# six2two-switch3.net
KiCad netlist of a schematic drawn in EAGLE
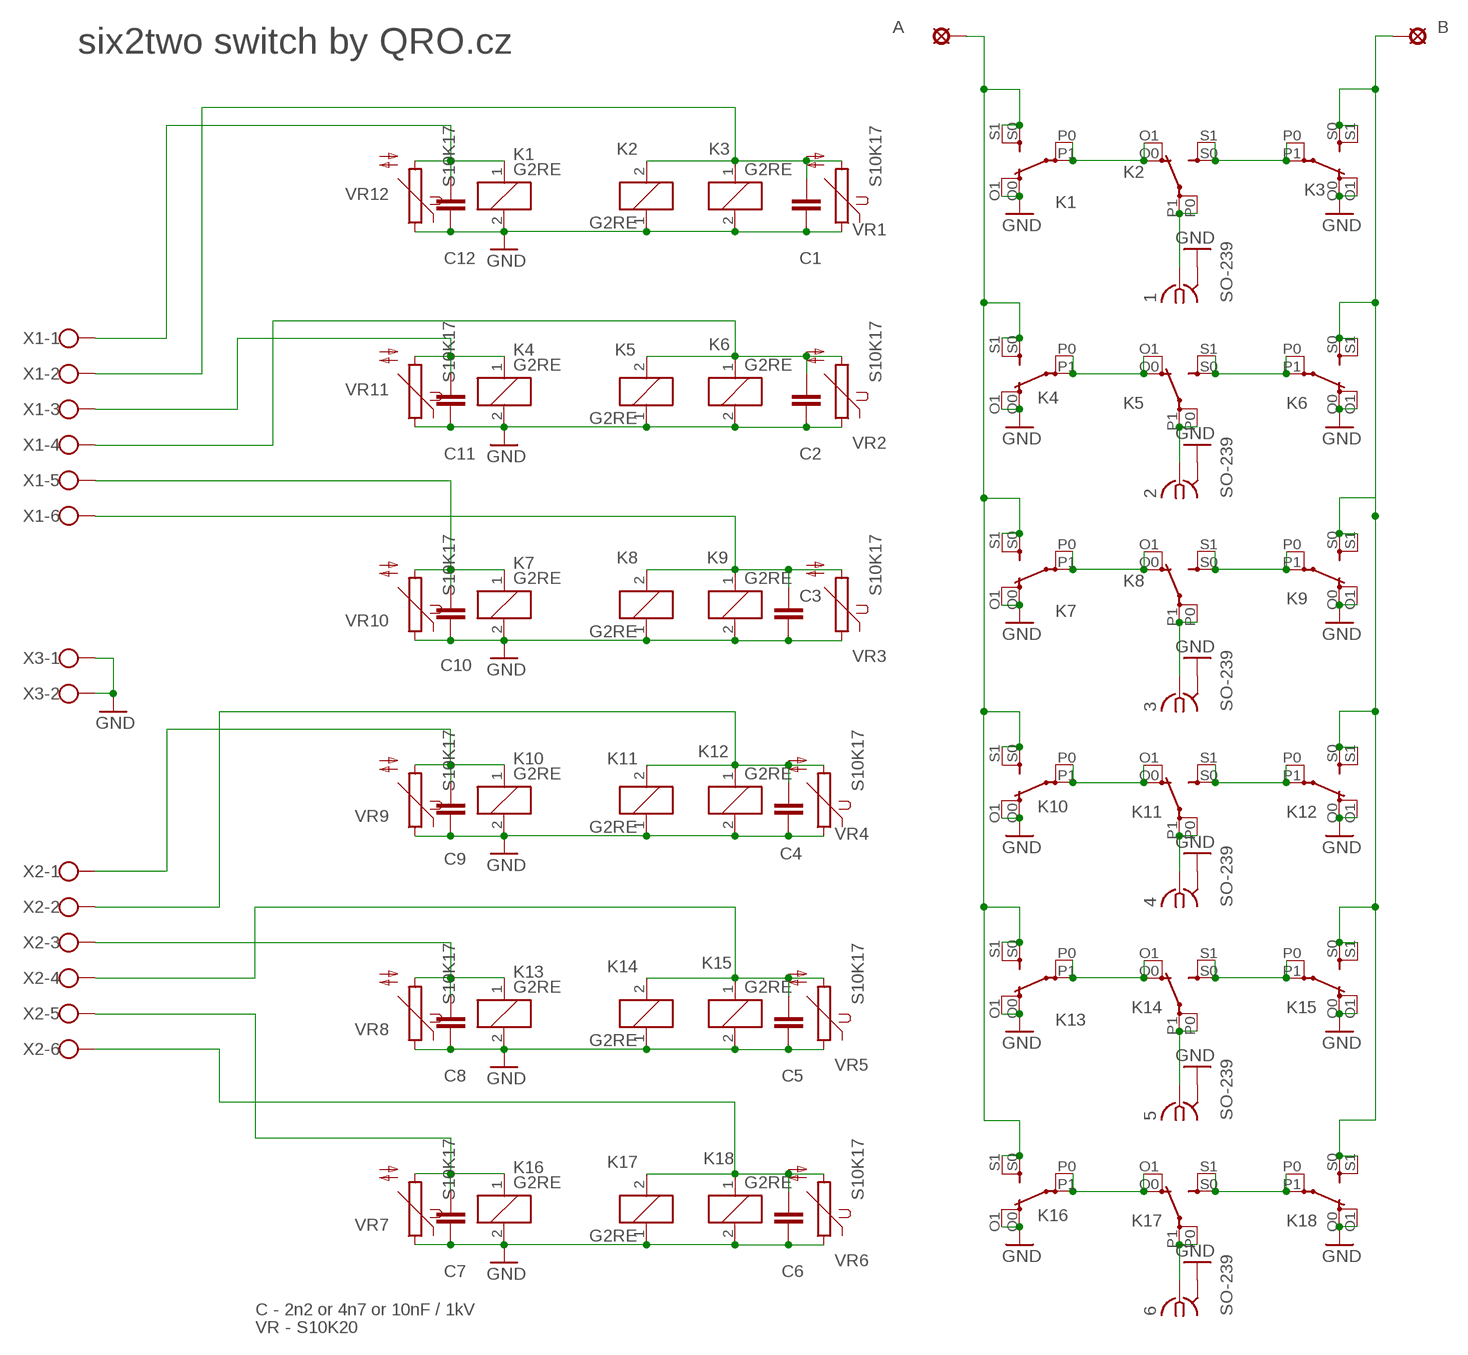
[diagram p0: schematic, sheet 1]

(export (version "E")
  (design (tool "Eeschema 10.0.6"))
  (components
    (comp (ref "1")
      (value "SO-239")
      (footprint "eagle-import:SO-239")
      (libsource (lib "eagle-import") (part "SO-239"))
    )
    (comp (ref "2")
      (value "SO-239")
      (footprint "eagle-import:SO-239")
      (libsource (lib "eagle-import") (part "SO-239"))
    )
    (comp (ref "3")
      (value "SO-239")
      (footprint "eagle-import:SO-239")
      (libsource (lib "eagle-import") (part "SO-239"))
    )
    (comp (ref "4")
      (value "SO-239")
      (footprint "eagle-import:SO-239")
      (libsource (lib "eagle-import") (part "SO-239"))
    )
    (comp (ref "5")
      (value "SO-239")
      (footprint "eagle-import:SO-239")
      (libsource (lib "eagle-import") (part "SO-239"))
    )
    (comp (ref "6")
      (value "SO-239")
      (footprint "eagle-import:SO-239")
      (libsource (lib "eagle-import") (part "SO-239"))
    )
    (comp (ref "A")
      (value "LSP13")
      (footprint "eagle-import:LSP13")
      (libsource (lib "eagle-import") (part "LSP13"))
    )
    (comp (ref "B")
      (value "LSP13")
      (footprint "eagle-import:LSP13")
      (libsource (lib "eagle-import") (part "LSP13"))
    )
    (comp (ref "C1")
      (value "C-EU075-032X103")
      (footprint "eagle-import:C075-032X103")
      (libsource (lib "eagle-import") (part "C-EU075-032X103"))
    )
    (comp (ref "C2")
      (value "C-EU075-032X103")
      (footprint "eagle-import:C075-032X103")
      (libsource (lib "eagle-import") (part "C-EU075-032X103"))
    )
    (comp (ref "C3")
      (value "C-EU075-032X103")
      (footprint "eagle-import:C075-032X103")
      (libsource (lib "eagle-import") (part "C-EU075-032X103"))
    )
    (comp (ref "C4")
      (value "C-EU075-032X103")
      (footprint "eagle-import:C075-032X103")
      (libsource (lib "eagle-import") (part "C-EU075-032X103"))
    )
    (comp (ref "C5")
      (value "C-EU075-032X103")
      (footprint "eagle-import:C075-032X103")
      (libsource (lib "eagle-import") (part "C-EU075-032X103"))
    )
    (comp (ref "C6")
      (value "C-EU075-032X103")
      (footprint "eagle-import:C075-032X103")
      (libsource (lib "eagle-import") (part "C-EU075-032X103"))
    )
    (comp (ref "C7")
      (value "C-EU075-032X103")
      (footprint "eagle-import:C075-032X103")
      (libsource (lib "eagle-import") (part "C-EU075-032X103"))
    )
    (comp (ref "C8")
      (value "C-EU075-032X103")
      (footprint "eagle-import:C075-032X103")
      (libsource (lib "eagle-import") (part "C-EU075-032X103"))
    )
    (comp (ref "C9")
      (value "C-EU075-032X103")
      (footprint "eagle-import:C075-032X103")
      (libsource (lib "eagle-import") (part "C-EU075-032X103"))
    )
    (comp (ref "C10")
      (value "C-EU075-032X103")
      (footprint "eagle-import:C075-032X103")
      (libsource (lib "eagle-import") (part "C-EU075-032X103"))
    )
    (comp (ref "C11")
      (value "C-EU075-032X103")
      (footprint "eagle-import:C075-032X103")
      (libsource (lib "eagle-import") (part "C-EU075-032X103"))
    )
    (comp (ref "C12")
      (value "C-EU075-032X103")
      (footprint "eagle-import:C075-032X103")
      (libsource (lib "eagle-import") (part "C-EU075-032X103"))
    )
    (comp (ref "K1")
      (value "G2RE")
      (footprint "eagle-import:G2RE")
      (libsource (lib "eagle-import") (part "G2RE"))
    )
    (comp (ref "K2")
      (value "G2RE")
      (footprint "eagle-import:G2RE")
      (libsource (lib "eagle-import") (part "G2RE"))
    )
    (comp (ref "K3")
      (value "G2RE")
      (footprint "eagle-import:G2RE")
      (libsource (lib "eagle-import") (part "G2RE"))
    )
    (comp (ref "K4")
      (value "G2RE")
      (footprint "eagle-import:G2RE")
      (libsource (lib "eagle-import") (part "G2RE"))
    )
    (comp (ref "K5")
      (value "G2RE")
      (footprint "eagle-import:G2RE")
      (libsource (lib "eagle-import") (part "G2RE"))
    )
    (comp (ref "K6")
      (value "G2RE")
      (footprint "eagle-import:G2RE")
      (libsource (lib "eagle-import") (part "G2RE"))
    )
    (comp (ref "K7")
      (value "G2RE")
      (footprint "eagle-import:G2RE")
      (libsource (lib "eagle-import") (part "G2RE"))
    )
    (comp (ref "K8")
      (value "G2RE")
      (footprint "eagle-import:G2RE")
      (libsource (lib "eagle-import") (part "G2RE"))
    )
    (comp (ref "K9")
      (value "G2RE")
      (footprint "eagle-import:G2RE")
      (libsource (lib "eagle-import") (part "G2RE"))
    )
    (comp (ref "K10")
      (value "G2RE")
      (footprint "eagle-import:G2RE")
      (libsource (lib "eagle-import") (part "G2RE"))
    )
    (comp (ref "K11")
      (value "G2RE")
      (footprint "eagle-import:G2RE")
      (libsource (lib "eagle-import") (part "G2RE"))
    )
    (comp (ref "K12")
      (value "G2RE")
      (footprint "eagle-import:G2RE")
      (libsource (lib "eagle-import") (part "G2RE"))
    )
    (comp (ref "K13")
      (value "G2RE")
      (footprint "eagle-import:G2RE")
      (libsource (lib "eagle-import") (part "G2RE"))
    )
    (comp (ref "K14")
      (value "G2RE")
      (footprint "eagle-import:G2RE")
      (libsource (lib "eagle-import") (part "G2RE"))
    )
    (comp (ref "K15")
      (value "G2RE")
      (footprint "eagle-import:G2RE")
      (libsource (lib "eagle-import") (part "G2RE"))
    )
    (comp (ref "K16")
      (value "G2RE")
      (footprint "eagle-import:G2RE")
      (libsource (lib "eagle-import") (part "G2RE"))
    )
    (comp (ref "K17")
      (value "G2RE")
      (footprint "eagle-import:G2RE")
      (libsource (lib "eagle-import") (part "G2RE"))
    )
    (comp (ref "K18")
      (value "G2RE")
      (footprint "eagle-import:G2RE")
      (libsource (lib "eagle-import") (part "G2RE"))
    )
    (comp (ref "VR1")
      (value "S10K17")
      (footprint "eagle-import:S10K17")
      (libsource (lib "eagle-import") (part "S10K17"))
    )
    (comp (ref "VR2")
      (value "S10K17")
      (footprint "eagle-import:S10K17")
      (libsource (lib "eagle-import") (part "S10K17"))
    )
    (comp (ref "VR3")
      (value "S10K17")
      (footprint "eagle-import:S10K17")
      (libsource (lib "eagle-import") (part "S10K17"))
    )
    (comp (ref "VR4")
      (value "S10K17")
      (footprint "eagle-import:S10K17")
      (libsource (lib "eagle-import") (part "S10K17"))
    )
    (comp (ref "VR5")
      (value "S10K17")
      (footprint "eagle-import:S10K17")
      (libsource (lib "eagle-import") (part "S10K17"))
    )
    (comp (ref "VR6")
      (value "S10K17")
      (footprint "eagle-import:S10K17")
      (libsource (lib "eagle-import") (part "S10K17"))
    )
    (comp (ref "VR7")
      (value "S10K17")
      (footprint "eagle-import:S10K17")
      (libsource (lib "eagle-import") (part "S10K17"))
    )
    (comp (ref "VR8")
      (value "S10K17")
      (footprint "eagle-import:S10K17")
      (libsource (lib "eagle-import") (part "S10K17"))
    )
    (comp (ref "VR9")
      (value "S10K17")
      (footprint "eagle-import:S10K17")
      (libsource (lib "eagle-import") (part "S10K17"))
    )
    (comp (ref "VR10")
      (value "S10K17")
      (footprint "eagle-import:S10K17")
      (libsource (lib "eagle-import") (part "S10K17"))
    )
    (comp (ref "VR11")
      (value "S10K17")
      (footprint "eagle-import:S10K17")
      (libsource (lib "eagle-import") (part "S10K17"))
    )
    (comp (ref "VR12")
      (value "S10K17")
      (footprint "eagle-import:S10K17")
      (libsource (lib "eagle-import") (part "S10K17"))
    )
    (comp (ref "X1")
      (value "W237-6")
      (footprint "eagle-import:W237-6")
      (libsource (lib "eagle-import") (part "W237-6"))
    )
    (comp (ref "X2")
      (value "W237-6")
      (footprint "eagle-import:W237-6")
      (libsource (lib "eagle-import") (part "W237-6"))
    )
    (comp (ref "X3")
      (value "W237-102")
      (footprint "eagle-import:W237-102")
      (fields (field (name "MPN") "237-102"))
      (libsource (lib "eagle-import") (part "W237-102"))
    )
  )
  (nets
    (net (code "1") (name "GND") (class "Default")
      (node (ref "1") (pin "P$2") (pinfunction "GND_P$2") (pintype "passive"))
      (node (ref "2") (pin "P$2") (pinfunction "GND_P$2") (pintype "passive"))
      (node (ref "3") (pin "P$2") (pinfunction "GND_P$2") (pintype "passive"))
      (node (ref "4") (pin "P$2") (pinfunction "GND_P$2") (pintype "passive"))
      (node (ref "5") (pin "P$2") (pinfunction "GND_P$2") (pintype "passive"))
      (node (ref "6") (pin "P$2") (pinfunction "GND_P$2") (pintype "passive"))
      (node (ref "C1") (pin "2") (pinfunction "2_2") (pintype "passive"))
      (node (ref "C10") (pin "2") (pinfunction "2_2") (pintype "passive"))
      (node (ref "C11") (pin "2") (pinfunction "2_2") (pintype "passive"))
      (node (ref "C12") (pin "2") (pinfunction "2_2") (pintype "passive"))
      (node (ref "C2") (pin "2") (pinfunction "2_2") (pintype "passive"))
      (node (ref "C3") (pin "2") (pinfunction "2_2") (pintype "passive"))
      (node (ref "C4") (pin "2") (pinfunction "2_2") (pintype "passive"))
      (node (ref "C5") (pin "2") (pinfunction "2_2") (pintype "passive"))
      (node (ref "C6") (pin "2") (pinfunction "2_2") (pintype "passive"))
      (node (ref "C7") (pin "2") (pinfunction "2_2") (pintype "passive"))
      (node (ref "C8") (pin "2") (pinfunction "2_2") (pintype "passive"))
      (node (ref "C9") (pin "2") (pinfunction "2_2") (pintype "passive"))
      (node (ref "K1") (pin "2") (pinfunction "2_2") (pintype "passive"))
      (node (ref "K1") (pin "O0") (pinfunction "O_O0") (pintype "passive"))
      (node (ref "K1") (pin "O1") (pinfunction "O_O1") (pintype "passive"))
      (node (ref "K10") (pin "2") (pinfunction "2_2") (pintype "passive"))
      (node (ref "K10") (pin "O0") (pinfunction "O_O0") (pintype "passive"))
      (node (ref "K10") (pin "O1") (pinfunction "O_O1") (pintype "passive"))
      (node (ref "K11") (pin "1") (pinfunction "1_1") (pintype "passive"))
      (node (ref "K12") (pin "2") (pinfunction "2_2") (pintype "passive"))
      (node (ref "K12") (pin "O0") (pinfunction "O_O0") (pintype "passive"))
      (node (ref "K12") (pin "O1") (pinfunction "O_O1") (pintype "passive"))
      (node (ref "K13") (pin "2") (pinfunction "2_2") (pintype "passive"))
      (node (ref "K13") (pin "O0") (pinfunction "O_O0") (pintype "passive"))
      (node (ref "K13") (pin "O1") (pinfunction "O_O1") (pintype "passive"))
      (node (ref "K14") (pin "1") (pinfunction "1_1") (pintype "passive"))
      (node (ref "K15") (pin "2") (pinfunction "2_2") (pintype "passive"))
      (node (ref "K15") (pin "O0") (pinfunction "O_O0") (pintype "passive"))
      (node (ref "K15") (pin "O1") (pinfunction "O_O1") (pintype "passive"))
      (node (ref "K16") (pin "2") (pinfunction "2_2") (pintype "passive"))
      (node (ref "K16") (pin "O0") (pinfunction "O_O0") (pintype "passive"))
      (node (ref "K16") (pin "O1") (pinfunction "O_O1") (pintype "passive"))
      (node (ref "K17") (pin "1") (pinfunction "1_1") (pintype "passive"))
      (node (ref "K18") (pin "2") (pinfunction "2_2") (pintype "passive"))
      (node (ref "K18") (pin "O0") (pinfunction "O_O0") (pintype "passive"))
      (node (ref "K18") (pin "O1") (pinfunction "O_O1") (pintype "passive"))
      (node (ref "K2") (pin "1") (pinfunction "1_1") (pintype "passive"))
      (node (ref "K3") (pin "2") (pinfunction "2_2") (pintype "passive"))
      (node (ref "K3") (pin "O0") (pinfunction "O_O0") (pintype "passive"))
      (node (ref "K3") (pin "O1") (pinfunction "O_O1") (pintype "passive"))
      (node (ref "K4") (pin "2") (pinfunction "2_2") (pintype "passive"))
      (node (ref "K4") (pin "O0") (pinfunction "O_O0") (pintype "passive"))
      (node (ref "K4") (pin "O1") (pinfunction "O_O1") (pintype "passive"))
      (node (ref "K5") (pin "1") (pinfunction "1_1") (pintype "passive"))
      (node (ref "K6") (pin "2") (pinfunction "2_2") (pintype "passive"))
      (node (ref "K6") (pin "O0") (pinfunction "O_O0") (pintype "passive"))
      (node (ref "K6") (pin "O1") (pinfunction "O_O1") (pintype "passive"))
      (node (ref "K7") (pin "2") (pinfunction "2_2") (pintype "passive"))
      (node (ref "K7") (pin "O0") (pinfunction "O_O0") (pintype "passive"))
      (node (ref "K7") (pin "O1") (pinfunction "O_O1") (pintype "passive"))
      (node (ref "K8") (pin "1") (pinfunction "1_1") (pintype "passive"))
      (node (ref "K9") (pin "2") (pinfunction "2_2") (pintype "passive"))
      (node (ref "K9") (pin "O0") (pinfunction "O_O0") (pintype "passive"))
      (node (ref "K9") (pin "O1") (pinfunction "O_O1") (pintype "passive"))
      (node (ref "VR1") (pin "1") (pinfunction "1_1") (pintype "passive"))
      (node (ref "VR10") (pin "1") (pinfunction "1_1") (pintype "passive"))
      (node (ref "VR11") (pin "1") (pinfunction "1_1") (pintype "passive"))
      (node (ref "VR12") (pin "1") (pinfunction "1_1") (pintype "passive"))
      (node (ref "VR2") (pin "1") (pinfunction "1_1") (pintype "passive"))
      (node (ref "VR3") (pin "1") (pinfunction "1_1") (pintype "passive"))
      (node (ref "VR4") (pin "1") (pinfunction "1_1") (pintype "passive"))
      (node (ref "VR5") (pin "1") (pinfunction "1_1") (pintype "passive"))
      (node (ref "VR6") (pin "1") (pinfunction "1_1") (pintype "passive"))
      (node (ref "VR7") (pin "1") (pinfunction "1_1") (pintype "passive"))
      (node (ref "VR8") (pin "1") (pinfunction "1_1") (pintype "passive"))
      (node (ref "VR9") (pin "1") (pinfunction "1_1") (pintype "passive"))
      (node (ref "X3") (pin "1") (pinfunction "KL_1") (pintype "passive"))
      (node (ref "X3") (pin "2") (pinfunction "KL_2") (pintype "passive"))
    )
    (net (code "2") (name "Net-(1-1)") (class "Default")
      (node (ref "1") (pin "P$1") (pinfunction "1_P$1") (pintype "passive"))
      (node (ref "K2") (pin "P0") (pinfunction "P_P0") (pintype "passive"))
      (node (ref "K2") (pin "P1") (pinfunction "P_P1") (pintype "passive"))
    )
    (net (code "3") (name "Net-(2-1)") (class "Default")
      (node (ref "2") (pin "P$1") (pinfunction "1_P$1") (pintype "passive"))
      (node (ref "K5") (pin "P0") (pinfunction "P_P0") (pintype "passive"))
      (node (ref "K5") (pin "P1") (pinfunction "P_P1") (pintype "passive"))
    )
    (net (code "4") (name "Net-(3-1)") (class "Default")
      (node (ref "3") (pin "P$1") (pinfunction "1_P$1") (pintype "passive"))
      (node (ref "K8") (pin "P0") (pinfunction "P_P0") (pintype "passive"))
      (node (ref "K8") (pin "P1") (pinfunction "P_P1") (pintype "passive"))
    )
    (net (code "5") (name "Net-(4-1)") (class "Default")
      (node (ref "4") (pin "P$1") (pinfunction "1_P$1") (pintype "passive"))
      (node (ref "K11") (pin "P0") (pinfunction "P_P0") (pintype "passive"))
      (node (ref "K11") (pin "P1") (pinfunction "P_P1") (pintype "passive"))
    )
    (net (code "6") (name "Net-(5-1)") (class "Default")
      (node (ref "5") (pin "P$1") (pinfunction "1_P$1") (pintype "passive"))
      (node (ref "K14") (pin "P0") (pinfunction "P_P0") (pintype "passive"))
      (node (ref "K14") (pin "P1") (pinfunction "P_P1") (pintype "passive"))
    )
    (net (code "7") (name "Net-(6-1)") (class "Default")
      (node (ref "6") (pin "P$1") (pinfunction "1_P$1") (pintype "passive"))
      (node (ref "K17") (pin "P0") (pinfunction "P_P0") (pintype "passive"))
      (node (ref "K17") (pin "P1") (pinfunction "P_P1") (pintype "passive"))
    )
    (net (code "8") (name "Net-(A-PadMP)") (class "Default")
      (node (ref "A") (pin "MP") (pinfunction "MP_MP") (pintype "passive"))
      (node (ref "K1") (pin "S0") (pinfunction "S_S0") (pintype "passive"))
      (node (ref "K1") (pin "S1") (pinfunction "S_S1") (pintype "passive"))
      (node (ref "K10") (pin "S0") (pinfunction "S_S0") (pintype "passive"))
      (node (ref "K10") (pin "S1") (pinfunction "S_S1") (pintype "passive"))
      (node (ref "K13") (pin "S0") (pinfunction "S_S0") (pintype "passive"))
      (node (ref "K13") (pin "S1") (pinfunction "S_S1") (pintype "passive"))
      (node (ref "K16") (pin "S0") (pinfunction "S_S0") (pintype "passive"))
      (node (ref "K16") (pin "S1") (pinfunction "S_S1") (pintype "passive"))
      (node (ref "K4") (pin "S0") (pinfunction "S_S0") (pintype "passive"))
      (node (ref "K4") (pin "S1") (pinfunction "S_S1") (pintype "passive"))
      (node (ref "K7") (pin "S0") (pinfunction "S_S0") (pintype "passive"))
      (node (ref "K7") (pin "S1") (pinfunction "S_S1") (pintype "passive"))
    )
    (net (code "9") (name "Net-(B-PadMP)") (class "Default")
      (node (ref "B") (pin "MP") (pinfunction "MP_MP") (pintype "passive"))
      (node (ref "K12") (pin "S0") (pinfunction "S_S0") (pintype "passive"))
      (node (ref "K12") (pin "S1") (pinfunction "S_S1") (pintype "passive"))
      (node (ref "K15") (pin "S0") (pinfunction "S_S0") (pintype "passive"))
      (node (ref "K15") (pin "S1") (pinfunction "S_S1") (pintype "passive"))
      (node (ref "K18") (pin "S0") (pinfunction "S_S0") (pintype "passive"))
      (node (ref "K18") (pin "S1") (pinfunction "S_S1") (pintype "passive"))
      (node (ref "K3") (pin "S0") (pinfunction "S_S0") (pintype "passive"))
      (node (ref "K3") (pin "S1") (pinfunction "S_S1") (pintype "passive"))
      (node (ref "K6") (pin "S0") (pinfunction "S_S0") (pintype "passive"))
      (node (ref "K6") (pin "S1") (pinfunction "S_S1") (pintype "passive"))
      (node (ref "K9") (pin "S0") (pinfunction "S_S0") (pintype "passive"))
      (node (ref "K9") (pin "S1") (pinfunction "S_S1") (pintype "passive"))
    )
    (net (code "10") (name "Net-(K1B-P-PadP0)") (class "Default")
      (node (ref "K1") (pin "P0") (pinfunction "P_P0") (pintype "passive"))
      (node (ref "K1") (pin "P1") (pinfunction "P_P1") (pintype "passive"))
      (node (ref "K2") (pin "O0") (pinfunction "O_O0") (pintype "passive"))
      (node (ref "K2") (pin "O1") (pinfunction "O_O1") (pintype "passive"))
    )
    (net (code "11") (name "Net-(K2B-S-PadS0)") (class "Default")
      (node (ref "K2") (pin "S0") (pinfunction "S_S0") (pintype "passive"))
      (node (ref "K2") (pin "S1") (pinfunction "S_S1") (pintype "passive"))
      (node (ref "K3") (pin "P0") (pinfunction "P_P0") (pintype "passive"))
      (node (ref "K3") (pin "P1") (pinfunction "P_P1") (pintype "passive"))
    )
    (net (code "12") (name "Net-(K4B-P-PadP0)") (class "Default")
      (node (ref "K4") (pin "P0") (pinfunction "P_P0") (pintype "passive"))
      (node (ref "K4") (pin "P1") (pinfunction "P_P1") (pintype "passive"))
      (node (ref "K5") (pin "O0") (pinfunction "O_O0") (pintype "passive"))
      (node (ref "K5") (pin "O1") (pinfunction "O_O1") (pintype "passive"))
    )
    (net (code "13") (name "Net-(K5B-S-PadS0)") (class "Default")
      (node (ref "K5") (pin "S0") (pinfunction "S_S0") (pintype "passive"))
      (node (ref "K5") (pin "S1") (pinfunction "S_S1") (pintype "passive"))
      (node (ref "K6") (pin "P0") (pinfunction "P_P0") (pintype "passive"))
      (node (ref "K6") (pin "P1") (pinfunction "P_P1") (pintype "passive"))
    )
    (net (code "14") (name "Net-(K7B-P-PadP0)") (class "Default")
      (node (ref "K7") (pin "P0") (pinfunction "P_P0") (pintype "passive"))
      (node (ref "K7") (pin "P1") (pinfunction "P_P1") (pintype "passive"))
      (node (ref "K8") (pin "O0") (pinfunction "O_O0") (pintype "passive"))
      (node (ref "K8") (pin "O1") (pinfunction "O_O1") (pintype "passive"))
    )
    (net (code "15") (name "Net-(K8B-S-PadS0)") (class "Default")
      (node (ref "K8") (pin "S0") (pinfunction "S_S0") (pintype "passive"))
      (node (ref "K8") (pin "S1") (pinfunction "S_S1") (pintype "passive"))
      (node (ref "K9") (pin "P0") (pinfunction "P_P0") (pintype "passive"))
      (node (ref "K9") (pin "P1") (pinfunction "P_P1") (pintype "passive"))
    )
    (net (code "16") (name "Net-(K10B-P-PadP0)") (class "Default")
      (node (ref "K10") (pin "P0") (pinfunction "P_P0") (pintype "passive"))
      (node (ref "K10") (pin "P1") (pinfunction "P_P1") (pintype "passive"))
      (node (ref "K11") (pin "O0") (pinfunction "O_O0") (pintype "passive"))
      (node (ref "K11") (pin "O1") (pinfunction "O_O1") (pintype "passive"))
    )
    (net (code "17") (name "Net-(K11B-S-PadS0)") (class "Default")
      (node (ref "K11") (pin "S0") (pinfunction "S_S0") (pintype "passive"))
      (node (ref "K11") (pin "S1") (pinfunction "S_S1") (pintype "passive"))
      (node (ref "K12") (pin "P0") (pinfunction "P_P0") (pintype "passive"))
      (node (ref "K12") (pin "P1") (pinfunction "P_P1") (pintype "passive"))
    )
    (net (code "18") (name "Net-(K13B-P-PadP0)") (class "Default")
      (node (ref "K13") (pin "P0") (pinfunction "P_P0") (pintype "passive"))
      (node (ref "K13") (pin "P1") (pinfunction "P_P1") (pintype "passive"))
      (node (ref "K14") (pin "O0") (pinfunction "O_O0") (pintype "passive"))
      (node (ref "K14") (pin "O1") (pinfunction "O_O1") (pintype "passive"))
    )
    (net (code "19") (name "Net-(K14B-S-PadS0)") (class "Default")
      (node (ref "K14") (pin "S0") (pinfunction "S_S0") (pintype "passive"))
      (node (ref "K14") (pin "S1") (pinfunction "S_S1") (pintype "passive"))
      (node (ref "K15") (pin "P0") (pinfunction "P_P0") (pintype "passive"))
      (node (ref "K15") (pin "P1") (pinfunction "P_P1") (pintype "passive"))
    )
    (net (code "20") (name "Net-(K16B-P-PadP0)") (class "Default")
      (node (ref "K16") (pin "P0") (pinfunction "P_P0") (pintype "passive"))
      (node (ref "K16") (pin "P1") (pinfunction "P_P1") (pintype "passive"))
      (node (ref "K17") (pin "O0") (pinfunction "O_O0") (pintype "passive"))
      (node (ref "K17") (pin "O1") (pinfunction "O_O1") (pintype "passive"))
    )
    (net (code "21") (name "Net-(K17B-S-PadS0)") (class "Default")
      (node (ref "K17") (pin "S0") (pinfunction "S_S0") (pintype "passive"))
      (node (ref "K17") (pin "S1") (pinfunction "S_S1") (pintype "passive"))
      (node (ref "K18") (pin "P0") (pinfunction "P_P0") (pintype "passive"))
      (node (ref "K18") (pin "P1") (pinfunction "P_P1") (pintype "passive"))
    )
    (net (code "22") (name "Net-(X1A-KL)") (class "Default")
      (node (ref "C12") (pin "1") (pinfunction "1_1") (pintype "passive"))
      (node (ref "K1") (pin "1") (pinfunction "1_1") (pintype "passive"))
      (node (ref "VR12") (pin "2") (pinfunction "2_2") (pintype "passive"))
      (node (ref "X1") (pin "1") (pinfunction "KL_1") (pintype "passive"))
    )
    (net (code "23") (name "Net-(X1B-KL)") (class "Default")
      (node (ref "C1") (pin "1") (pinfunction "1_1") (pintype "passive"))
      (node (ref "K2") (pin "2") (pinfunction "2_2") (pintype "passive"))
      (node (ref "K3") (pin "1") (pinfunction "1_1") (pintype "passive"))
      (node (ref "VR1") (pin "2") (pinfunction "2_2") (pintype "passive"))
      (node (ref "X1") (pin "2") (pinfunction "KL_2") (pintype "passive"))
    )
    (net (code "24") (name "Net-(X1C-KL)") (class "Default")
      (node (ref "C11") (pin "1") (pinfunction "1_1") (pintype "passive"))
      (node (ref "K4") (pin "1") (pinfunction "1_1") (pintype "passive"))
      (node (ref "VR11") (pin "2") (pinfunction "2_2") (pintype "passive"))
      (node (ref "X1") (pin "3") (pinfunction "KL_3") (pintype "passive"))
    )
    (net (code "25") (name "Net-(X1D-KL)") (class "Default")
      (node (ref "C2") (pin "1") (pinfunction "1_1") (pintype "passive"))
      (node (ref "K5") (pin "2") (pinfunction "2_2") (pintype "passive"))
      (node (ref "K6") (pin "1") (pinfunction "1_1") (pintype "passive"))
      (node (ref "VR2") (pin "2") (pinfunction "2_2") (pintype "passive"))
      (node (ref "X1") (pin "4") (pinfunction "KL_4") (pintype "passive"))
    )
    (net (code "26") (name "Net-(X1E-KL)") (class "Default")
      (node (ref "C10") (pin "1") (pinfunction "1_1") (pintype "passive"))
      (node (ref "K7") (pin "1") (pinfunction "1_1") (pintype "passive"))
      (node (ref "VR10") (pin "2") (pinfunction "2_2") (pintype "passive"))
      (node (ref "X1") (pin "5") (pinfunction "KL_5") (pintype "passive"))
    )
    (net (code "27") (name "Net-(X1F-KL)") (class "Default")
      (node (ref "C3") (pin "1") (pinfunction "1_1") (pintype "passive"))
      (node (ref "K8") (pin "2") (pinfunction "2_2") (pintype "passive"))
      (node (ref "K9") (pin "1") (pinfunction "1_1") (pintype "passive"))
      (node (ref "VR3") (pin "2") (pinfunction "2_2") (pintype "passive"))
      (node (ref "X1") (pin "6") (pinfunction "KL_6") (pintype "passive"))
    )
    (net (code "28") (name "Net-(X2A-KL)") (class "Default")
      (node (ref "C9") (pin "1") (pinfunction "1_1") (pintype "passive"))
      (node (ref "K10") (pin "1") (pinfunction "1_1") (pintype "passive"))
      (node (ref "VR9") (pin "2") (pinfunction "2_2") (pintype "passive"))
      (node (ref "X2") (pin "1") (pinfunction "KL_1") (pintype "passive"))
    )
    (net (code "29") (name "Net-(X2B-KL)") (class "Default")
      (node (ref "C4") (pin "1") (pinfunction "1_1") (pintype "passive"))
      (node (ref "K11") (pin "2") (pinfunction "2_2") (pintype "passive"))
      (node (ref "K12") (pin "1") (pinfunction "1_1") (pintype "passive"))
      (node (ref "VR4") (pin "2") (pinfunction "2_2") (pintype "passive"))
      (node (ref "X2") (pin "2") (pinfunction "KL_2") (pintype "passive"))
    )
    (net (code "30") (name "Net-(X2C-KL)") (class "Default")
      (node (ref "C8") (pin "1") (pinfunction "1_1") (pintype "passive"))
      (node (ref "K13") (pin "1") (pinfunction "1_1") (pintype "passive"))
      (node (ref "VR8") (pin "2") (pinfunction "2_2") (pintype "passive"))
      (node (ref "X2") (pin "3") (pinfunction "KL_3") (pintype "passive"))
    )
    (net (code "31") (name "Net-(X2D-KL)") (class "Default")
      (node (ref "C5") (pin "1") (pinfunction "1_1") (pintype "passive"))
      (node (ref "K14") (pin "2") (pinfunction "2_2") (pintype "passive"))
      (node (ref "K15") (pin "1") (pinfunction "1_1") (pintype "passive"))
      (node (ref "VR5") (pin "2") (pinfunction "2_2") (pintype "passive"))
      (node (ref "X2") (pin "4") (pinfunction "KL_4") (pintype "passive"))
    )
    (net (code "32") (name "Net-(X2E-KL)") (class "Default")
      (node (ref "C7") (pin "1") (pinfunction "1_1") (pintype "passive"))
      (node (ref "K16") (pin "1") (pinfunction "1_1") (pintype "passive"))
      (node (ref "VR7") (pin "2") (pinfunction "2_2") (pintype "passive"))
      (node (ref "X2") (pin "5") (pinfunction "KL_5") (pintype "passive"))
    )
    (net (code "33") (name "Net-(X2F-KL)") (class "Default")
      (node (ref "C6") (pin "1") (pinfunction "1_1") (pintype "passive"))
      (node (ref "K17") (pin "2") (pinfunction "2_2") (pintype "passive"))
      (node (ref "K18") (pin "1") (pinfunction "1_1") (pintype "passive"))
      (node (ref "VR6") (pin "2") (pinfunction "2_2") (pintype "passive"))
      (node (ref "X2") (pin "6") (pinfunction "KL_6") (pintype "passive"))
    )
  )
)
